# filters_V1_1_Carlos.net
KiCad netlist of a schematic drawn in EAGLE
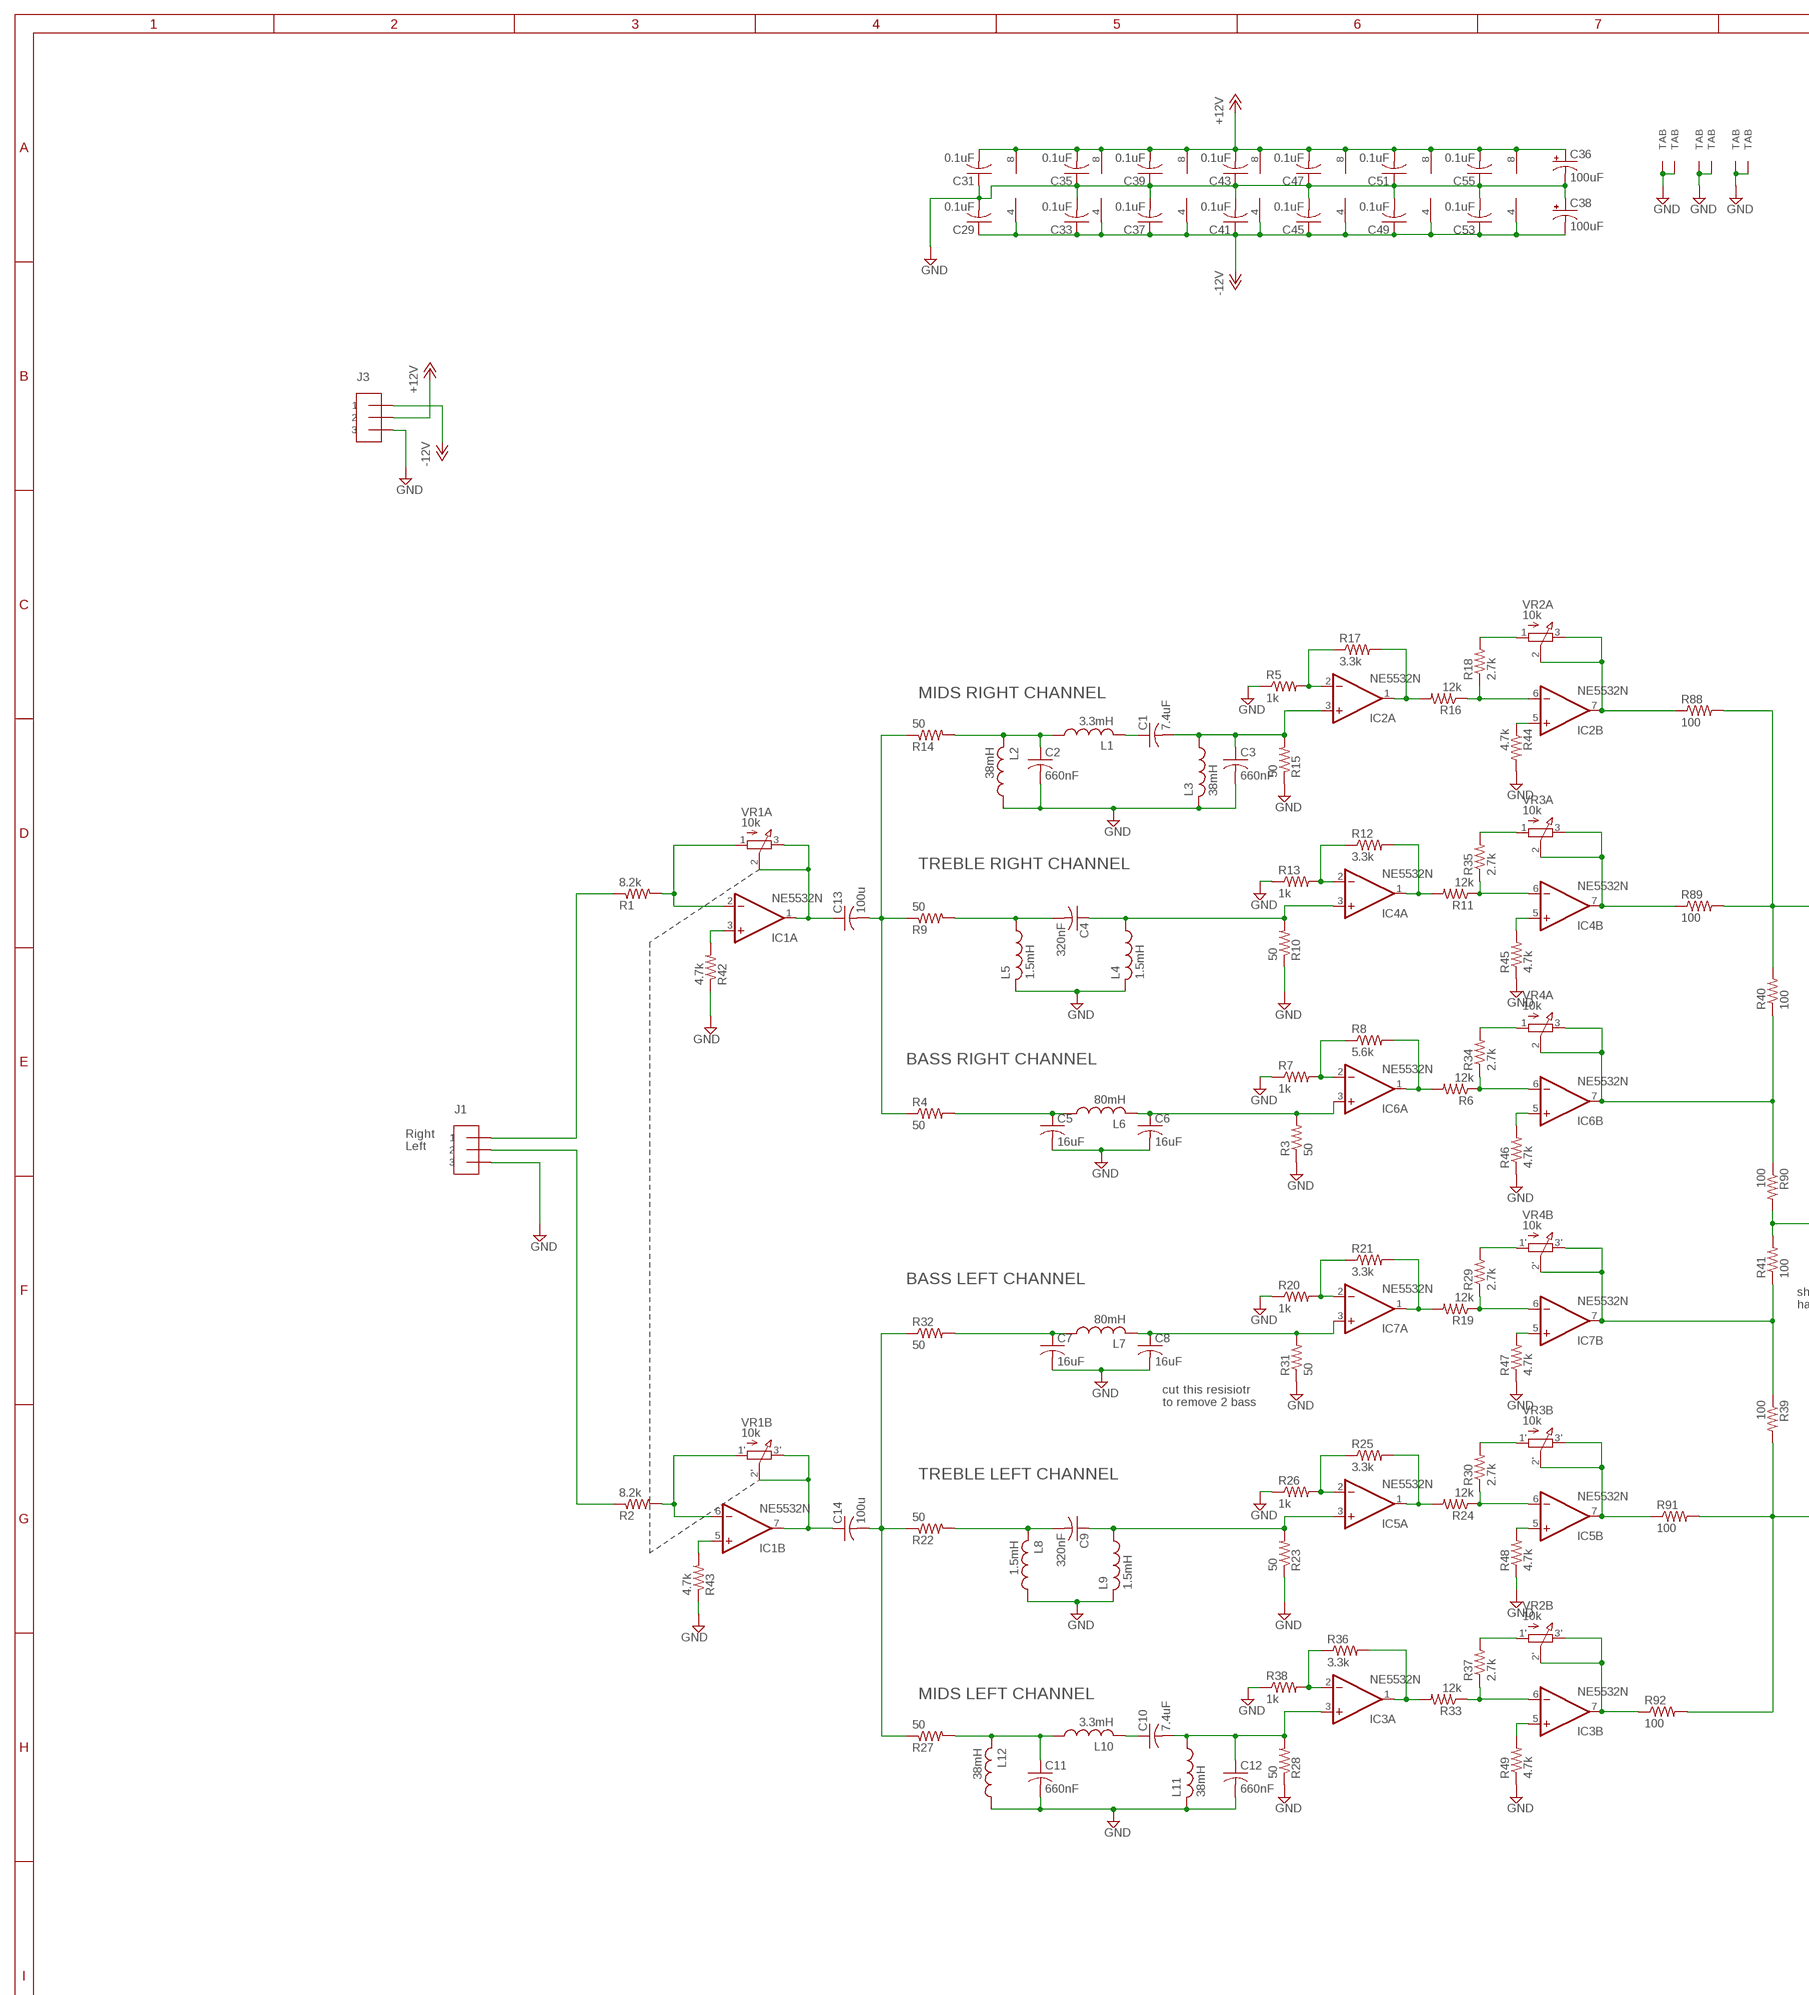
[diagram p0: schematic, sheet 1, part 1 of 2]
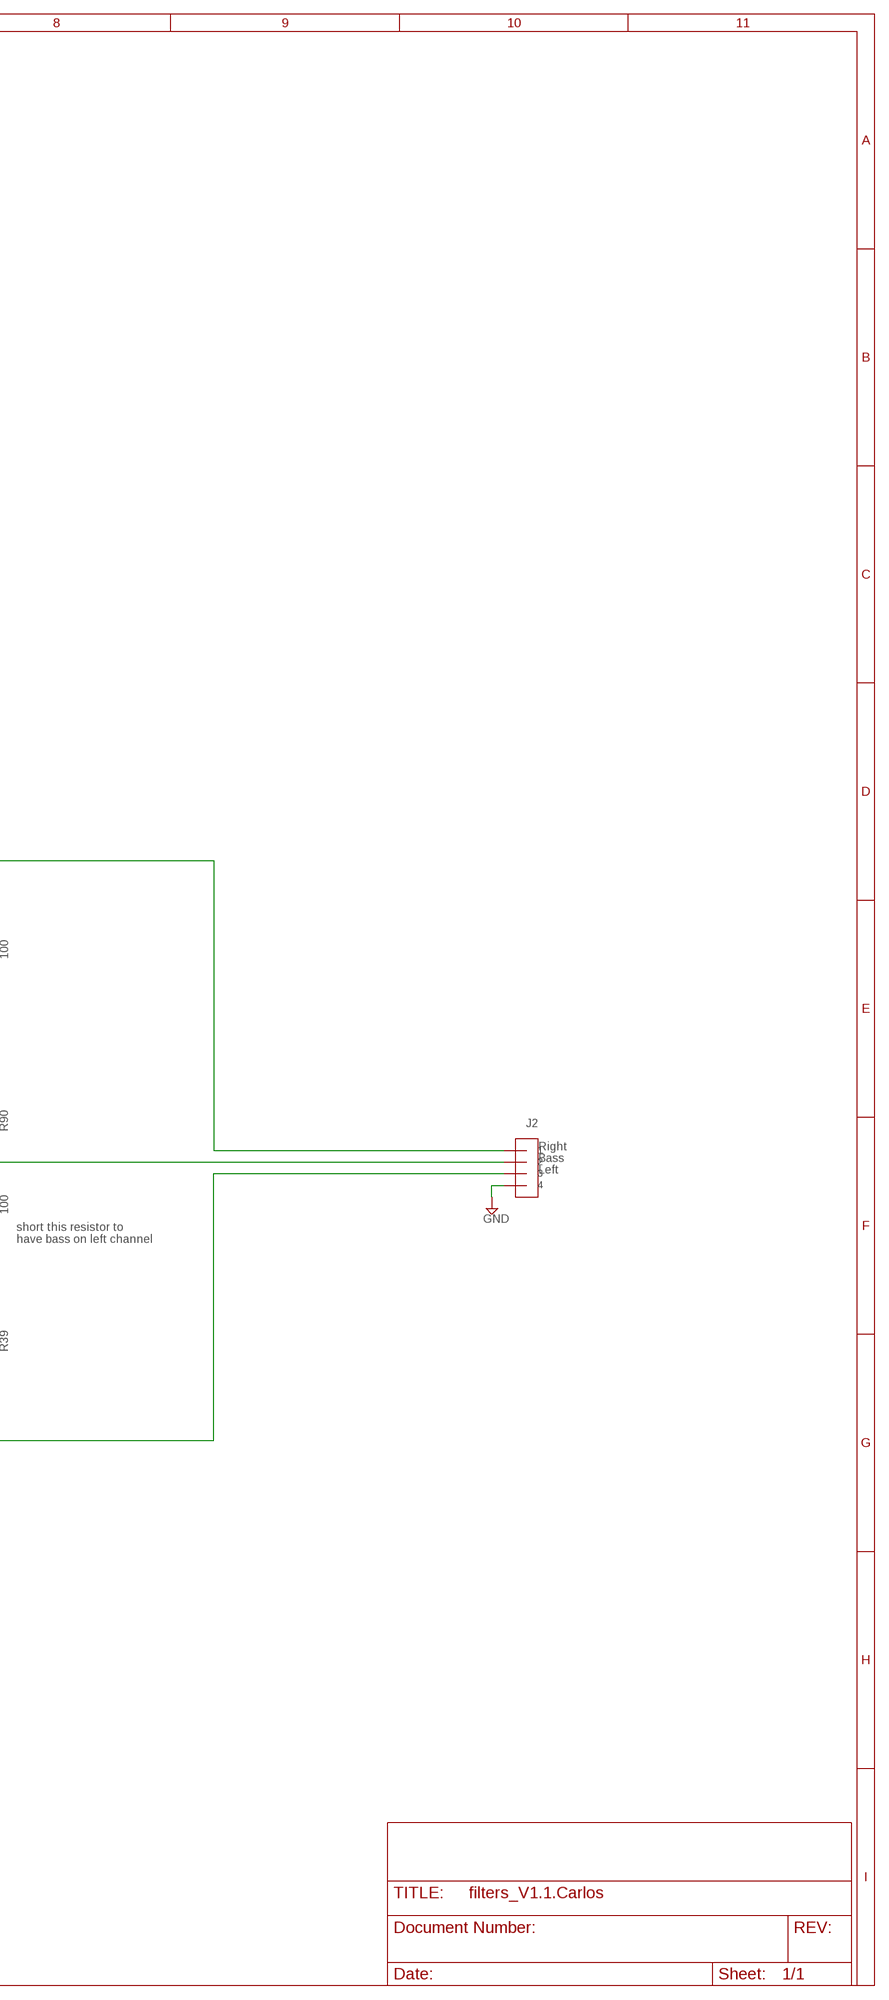
[diagram p1: schematic, sheet 1, part 2 of 2]

(export (version "E")
  (design (tool "Eeschema 10.0.6"))
  (components
    (comp (ref "C1")
      (value "7.4uF")
      (footprint "eagle-import:C050-024X044")
      (libsource (lib "eagle-import") (part "C-US050-024X044"))
    )
    (comp (ref "C2")
      (value "660nF")
      (footprint "eagle-import:C050-024X044")
      (libsource (lib "eagle-import") (part "C-US050-024X044"))
    )
    (comp (ref "C3")
      (value "660nF")
      (footprint "eagle-import:C050-024X044")
      (libsource (lib "eagle-import") (part "C-US050-024X044"))
    )
    (comp (ref "C4")
      (value "320nF")
      (footprint "eagle-import:C050-024X044")
      (libsource (lib "eagle-import") (part "C-US050-024X044"))
    )
    (comp (ref "C5")
      (value "16uF")
      (footprint "eagle-import:C050-024X044")
      (libsource (lib "eagle-import") (part "C-US050-024X044"))
    )
    (comp (ref "C6")
      (value "16uF")
      (footprint "eagle-import:C050-024X044")
      (libsource (lib "eagle-import") (part "C-US050-024X044"))
    )
    (comp (ref "C7")
      (value "16uF")
      (footprint "eagle-import:C050-024X044")
      (libsource (lib "eagle-import") (part "C-US050-024X044"))
    )
    (comp (ref "C8")
      (value "16uF")
      (footprint "eagle-import:C050-024X044")
      (libsource (lib "eagle-import") (part "C-US050-024X044"))
    )
    (comp (ref "C9")
      (value "320nF")
      (footprint "eagle-import:C050-024X044")
      (libsource (lib "eagle-import") (part "C-US050-024X044"))
    )
    (comp (ref "C10")
      (value "7.4uF")
      (footprint "eagle-import:C050-024X044")
      (libsource (lib "eagle-import") (part "C-US050-024X044"))
    )
    (comp (ref "C11")
      (value "660nF")
      (footprint "eagle-import:C050-024X044")
      (libsource (lib "eagle-import") (part "C-US050-024X044"))
    )
    (comp (ref "C12")
      (value "660nF")
      (footprint "eagle-import:C050-024X044")
      (libsource (lib "eagle-import") (part "C-US050-024X044"))
    )
    (comp (ref "C13")
      (value "100u")
      (footprint "eagle-import:C050-024X044")
      (libsource (lib "eagle-import") (part "C-US050-024X044"))
    )
    (comp (ref "C14")
      (value "100u")
      (footprint "eagle-import:C050-024X044")
      (libsource (lib "eagle-import") (part "C-US050-024X044"))
    )
    (comp (ref "C29")
      (value "0.1uF")
      (footprint "eagle-import:C050-024X044")
      (libsource (lib "eagle-import") (part "C-US050-024X044"))
    )
    (comp (ref "C31")
      (value "0.1uF")
      (footprint "eagle-import:C050-024X044")
      (libsource (lib "eagle-import") (part "C-US050-024X044"))
    )
    (comp (ref "C33")
      (value "0.1uF")
      (footprint "eagle-import:C050-024X044")
      (libsource (lib "eagle-import") (part "C-US050-024X044"))
    )
    (comp (ref "C35")
      (value "0.1uF")
      (footprint "eagle-import:C050-024X044")
      (libsource (lib "eagle-import") (part "C-US050-024X044"))
    )
    (comp (ref "C36")
      (value "100uF")
      (footprint "eagle-import:E2,5-6")
      (libsource (lib "eagle-import") (part "CPOL-USE2.5-6"))
    )
    (comp (ref "C37")
      (value "0.1uF")
      (footprint "eagle-import:C050-024X044")
      (libsource (lib "eagle-import") (part "C-US050-024X044"))
    )
    (comp (ref "C38")
      (value "100uF")
      (footprint "eagle-import:E2,5-6")
      (libsource (lib "eagle-import") (part "CPOL-USE2.5-6"))
    )
    (comp (ref "C39")
      (value "0.1uF")
      (footprint "eagle-import:C050-024X044")
      (libsource (lib "eagle-import") (part "C-US050-024X044"))
    )
    (comp (ref "C41")
      (value "0.1uF")
      (footprint "eagle-import:C050-024X044")
      (libsource (lib "eagle-import") (part "C-US050-024X044"))
    )
    (comp (ref "C43")
      (value "0.1uF")
      (footprint "eagle-import:C050-024X044")
      (libsource (lib "eagle-import") (part "C-US050-024X044"))
    )
    (comp (ref "C45")
      (value "0.1uF")
      (footprint "eagle-import:C050-024X044")
      (libsource (lib "eagle-import") (part "C-US050-024X044"))
    )
    (comp (ref "C47")
      (value "0.1uF")
      (footprint "eagle-import:C050-024X044")
      (libsource (lib "eagle-import") (part "C-US050-024X044"))
    )
    (comp (ref "C49")
      (value "0.1uF")
      (footprint "eagle-import:C050-024X044")
      (libsource (lib "eagle-import") (part "C-US050-024X044"))
    )
    (comp (ref "C51")
      (value "0.1uF")
      (footprint "eagle-import:C050-024X044")
      (libsource (lib "eagle-import") (part "C-US050-024X044"))
    )
    (comp (ref "C53")
      (value "0.1uF")
      (footprint "eagle-import:C050-024X044")
      (libsource (lib "eagle-import") (part "C-US050-024X044"))
    )
    (comp (ref "C55")
      (value "0.1uF")
      (footprint "eagle-import:C050-024X044")
      (libsource (lib "eagle-import") (part "C-US050-024X044"))
    )
    (comp (ref "IC1")
      (value "NE5532N")
      (footprint "eagle-import:DIL08")
      (libsource (lib "eagle-import") (part "NE5532N"))
    )
    (comp (ref "IC2")
      (value "NE5532N")
      (footprint "eagle-import:DIL08")
      (libsource (lib "eagle-import") (part "NE5532N"))
    )
    (comp (ref "IC3")
      (value "NE5532N")
      (footprint "eagle-import:DIL08")
      (libsource (lib "eagle-import") (part "NE5532N"))
    )
    (comp (ref "IC4")
      (value "NE5532N")
      (footprint "eagle-import:DIL08")
      (libsource (lib "eagle-import") (part "NE5532N"))
    )
    (comp (ref "IC5")
      (value "NE5532N")
      (footprint "eagle-import:DIL08")
      (libsource (lib "eagle-import") (part "NE5532N"))
    )
    (comp (ref "IC6")
      (value "NE5532N")
      (footprint "eagle-import:DIL08")
      (libsource (lib "eagle-import") (part "NE5532N"))
    )
    (comp (ref "IC7")
      (value "NE5532N")
      (footprint "eagle-import:DIL08")
      (libsource (lib "eagle-import") (part "NE5532N"))
    )
    (comp (ref "J1")
      (value "3_PIN_AMPCONN")
      (footprint "eagle-import:3_PIN_AMPCONN")
      (libsource (lib "eagle-import") (part "3_PIN_AMPCONN"))
    )
    (comp (ref "J2")
      (value "4_PIN_AMPCONN")
      (footprint "eagle-import:4_PIN_AMPCON")
      (libsource (lib "eagle-import") (part "4_PIN_AMPCONN"))
    )
    (comp (ref "J3")
      (value "3_PIN_AMPCONN")
      (footprint "eagle-import:3_PIN_AMPCONN")
      (libsource (lib "eagle-import") (part "3_PIN_AMPCONN"))
    )
    (comp (ref "L1")
      (value "3.3mH")
      (footprint "eagle-import:6000-XXXX-RC")
      (libsource (lib "eagle-import") (part "L-US6000-XXX-RC"))
    )
    (comp (ref "L2")
      (value "38mH")
      (footprint "eagle-import:6000-XXXX-RC")
      (libsource (lib "eagle-import") (part "L-US6000-XXX-RC"))
    )
    (comp (ref "L3")
      (value "38mH")
      (footprint "eagle-import:6000-XXXX-RC")
      (libsource (lib "eagle-import") (part "L-US6000-XXX-RC"))
    )
    (comp (ref "L4")
      (value "1.5mH")
      (footprint "eagle-import:6000-XXXX-RC")
      (libsource (lib "eagle-import") (part "L-US6000-XXX-RC"))
    )
    (comp (ref "L5")
      (value "1.5mH")
      (footprint "eagle-import:6000-XXXX-RC")
      (libsource (lib "eagle-import") (part "L-US6000-XXX-RC"))
    )
    (comp (ref "L6")
      (value "80mH")
      (footprint "eagle-import:6000-XXXX-RC")
      (libsource (lib "eagle-import") (part "L-US6000-XXX-RC"))
    )
    (comp (ref "L7")
      (value "80mH")
      (footprint "eagle-import:6000-XXXX-RC")
      (libsource (lib "eagle-import") (part "L-US6000-XXX-RC"))
    )
    (comp (ref "L8")
      (value "1.5mH")
      (footprint "eagle-import:6000-XXXX-RC")
      (libsource (lib "eagle-import") (part "L-US6000-XXX-RC"))
    )
    (comp (ref "L9")
      (value "1.5mH")
      (footprint "eagle-import:6000-XXXX-RC")
      (libsource (lib "eagle-import") (part "L-US6000-XXX-RC"))
    )
    (comp (ref "L10")
      (value "3.3mH")
      (footprint "eagle-import:6000-XXXX-RC")
      (libsource (lib "eagle-import") (part "L-US6000-XXX-RC"))
    )
    (comp (ref "L11")
      (value "38mH")
      (footprint "eagle-import:6000-XXXX-RC")
      (libsource (lib "eagle-import") (part "L-US6000-XXX-RC"))
    )
    (comp (ref "L12")
      (value "38mH")
      (footprint "eagle-import:6000-XXXX-RC")
      (libsource (lib "eagle-import") (part "L-US6000-XXX-RC"))
    )
    (comp (ref "R1")
      (value "8.2k")
      (footprint "eagle-import:0204V")
      (libsource (lib "eagle-import") (part "R-US_0204/2V"))
    )
    (comp (ref "R2")
      (value "8.2k")
      (footprint "eagle-import:0204V")
      (libsource (lib "eagle-import") (part "R-US_0204/2V"))
    )
    (comp (ref "R3")
      (value "50")
      (footprint "eagle-import:0204V")
      (libsource (lib "eagle-import") (part "R-US_0204/2V"))
    )
    (comp (ref "R4")
      (value "50")
      (footprint "eagle-import:0204V")
      (libsource (lib "eagle-import") (part "R-US_0204/2V"))
    )
    (comp (ref "R5")
      (value "1k")
      (footprint "eagle-import:0204V")
      (libsource (lib "eagle-import") (part "R-US_0204/2V"))
    )
    (comp (ref "R6")
      (value "12k")
      (footprint "eagle-import:0204V")
      (libsource (lib "eagle-import") (part "R-US_0204/2V"))
    )
    (comp (ref "R7")
      (value "1k")
      (footprint "eagle-import:0204V")
      (libsource (lib "eagle-import") (part "R-US_0204/2V"))
    )
    (comp (ref "R8")
      (value "5.6k")
      (footprint "eagle-import:0204V")
      (libsource (lib "eagle-import") (part "R-US_0204/2V"))
    )
    (comp (ref "R9")
      (value "50")
      (footprint "eagle-import:0204V")
      (libsource (lib "eagle-import") (part "R-US_0204/2V"))
    )
    (comp (ref "R10")
      (value "50")
      (footprint "eagle-import:0204V")
      (libsource (lib "eagle-import") (part "R-US_0204/2V"))
    )
    (comp (ref "R11")
      (value "12k")
      (footprint "eagle-import:0204V")
      (libsource (lib "eagle-import") (part "R-US_0204/2V"))
    )
    (comp (ref "R12")
      (value "3.3k")
      (footprint "eagle-import:0204V")
      (libsource (lib "eagle-import") (part "R-US_0204/2V"))
    )
    (comp (ref "R13")
      (value "1k")
      (footprint "eagle-import:0204V")
      (libsource (lib "eagle-import") (part "R-US_0204/2V"))
    )
    (comp (ref "R14")
      (value "50")
      (footprint "eagle-import:0204V")
      (libsource (lib "eagle-import") (part "R-US_0204/2V"))
    )
    (comp (ref "R15")
      (value "50")
      (footprint "eagle-import:0204V")
      (libsource (lib "eagle-import") (part "R-US_0204/2V"))
    )
    (comp (ref "R16")
      (value "12k")
      (footprint "eagle-import:0204V")
      (libsource (lib "eagle-import") (part "R-US_0204/2V"))
    )
    (comp (ref "R17")
      (value "3.3k")
      (footprint "eagle-import:0204V")
      (libsource (lib "eagle-import") (part "R-US_0204/2V"))
    )
    (comp (ref "R18")
      (value "2.7k")
      (footprint "eagle-import:0204V")
      (libsource (lib "eagle-import") (part "R-US_0204/2V"))
    )
    (comp (ref "R19")
      (value "12k")
      (footprint "eagle-import:0204V")
      (libsource (lib "eagle-import") (part "R-US_0204/2V"))
    )
    (comp (ref "R20")
      (value "1k")
      (footprint "eagle-import:0204V")
      (libsource (lib "eagle-import") (part "R-US_0204/2V"))
    )
    (comp (ref "R21")
      (value "3.3k")
      (footprint "eagle-import:0204V")
      (libsource (lib "eagle-import") (part "R-US_0204/2V"))
    )
    (comp (ref "R22")
      (value "50")
      (footprint "eagle-import:0204V")
      (libsource (lib "eagle-import") (part "R-US_0204/2V"))
    )
    (comp (ref "R23")
      (value "50")
      (footprint "eagle-import:0204V")
      (libsource (lib "eagle-import") (part "R-US_0204/2V"))
    )
    (comp (ref "R24")
      (value "12k")
      (footprint "eagle-import:0204V")
      (libsource (lib "eagle-import") (part "R-US_0204/2V"))
    )
    (comp (ref "R25")
      (value "3.3k")
      (footprint "eagle-import:0204V")
      (libsource (lib "eagle-import") (part "R-US_0204/2V"))
    )
    (comp (ref "R26")
      (value "1k")
      (footprint "eagle-import:0204V")
      (libsource (lib "eagle-import") (part "R-US_0204/2V"))
    )
    (comp (ref "R27")
      (value "50")
      (footprint "eagle-import:0204V")
      (libsource (lib "eagle-import") (part "R-US_0204/2V"))
    )
    (comp (ref "R28")
      (value "50")
      (footprint "eagle-import:0204V")
      (libsource (lib "eagle-import") (part "R-US_0204/2V"))
    )
    (comp (ref "R29")
      (value "2.7k")
      (footprint "eagle-import:0204V")
      (libsource (lib "eagle-import") (part "R-US_0204/2V"))
    )
    (comp (ref "R30")
      (value "2.7k")
      (footprint "eagle-import:0204V")
      (libsource (lib "eagle-import") (part "R-US_0204/2V"))
    )
    (comp (ref "R31")
      (value "50")
      (footprint "eagle-import:0204V")
      (libsource (lib "eagle-import") (part "R-US_0204/2V"))
    )
    (comp (ref "R32")
      (value "50")
      (footprint "eagle-import:0204V")
      (libsource (lib "eagle-import") (part "R-US_0204/2V"))
    )
    (comp (ref "R33")
      (value "12k")
      (footprint "eagle-import:0204V")
      (libsource (lib "eagle-import") (part "R-US_0204/2V"))
    )
    (comp (ref "R34")
      (value "2.7k")
      (footprint "eagle-import:0204V")
      (libsource (lib "eagle-import") (part "R-US_0204/2V"))
    )
    (comp (ref "R35")
      (value "2.7k")
      (footprint "eagle-import:0204V")
      (libsource (lib "eagle-import") (part "R-US_0204/2V"))
    )
    (comp (ref "R36")
      (value "3.3k")
      (footprint "eagle-import:0204V")
      (libsource (lib "eagle-import") (part "R-US_0204/2V"))
    )
    (comp (ref "R37")
      (value "2.7k")
      (footprint "eagle-import:0204V")
      (libsource (lib "eagle-import") (part "R-US_0204/2V"))
    )
    (comp (ref "R38")
      (value "1k")
      (footprint "eagle-import:0204V")
      (libsource (lib "eagle-import") (part "R-US_0204/2V"))
    )
    (comp (ref "R39")
      (value "100")
      (footprint "eagle-import:0204V")
      (libsource (lib "eagle-import") (part "R-US_0204/2V"))
    )
    (comp (ref "R40")
      (value "100")
      (footprint "eagle-import:0204V")
      (libsource (lib "eagle-import") (part "R-US_0204/2V"))
    )
    (comp (ref "R41")
      (value "100")
      (footprint "eagle-import:0204V")
      (libsource (lib "eagle-import") (part "R-US_0204/2V"))
    )
    (comp (ref "R42")
      (value "4.7k")
      (footprint "eagle-import:0204V")
      (libsource (lib "eagle-import") (part "R-US_0204/2V"))
    )
    (comp (ref "R43")
      (value "4.7k")
      (footprint "eagle-import:0204V")
      (libsource (lib "eagle-import") (part "R-US_0204/2V"))
    )
    (comp (ref "R44")
      (value "4.7k")
      (footprint "eagle-import:0204V")
      (libsource (lib "eagle-import") (part "R-US_0204/2V"))
    )
    (comp (ref "R45")
      (value "4.7k")
      (footprint "eagle-import:0204V")
      (libsource (lib "eagle-import") (part "R-US_0204/2V"))
    )
    (comp (ref "R46")
      (value "4.7k")
      (footprint "eagle-import:0204V")
      (libsource (lib "eagle-import") (part "R-US_0204/2V"))
    )
    (comp (ref "R47")
      (value "4.7k")
      (footprint "eagle-import:0204V")
      (libsource (lib "eagle-import") (part "R-US_0204/2V"))
    )
    (comp (ref "R48")
      (value "4.7k")
      (footprint "eagle-import:0204V")
      (libsource (lib "eagle-import") (part "R-US_0204/2V"))
    )
    (comp (ref "R49")
      (value "4.7k")
      (footprint "eagle-import:0204V")
      (libsource (lib "eagle-import") (part "R-US_0204/2V"))
    )
    (comp (ref "R88")
      (value "100")
      (footprint "eagle-import:0204V")
      (libsource (lib "eagle-import") (part "R-US_0204/2V"))
    )
    (comp (ref "R89")
      (value "100")
      (footprint "eagle-import:0204V")
      (libsource (lib "eagle-import") (part "R-US_0204/2V"))
    )
    (comp (ref "R90")
      (value "100")
      (footprint "eagle-import:0204V")
      (libsource (lib "eagle-import") (part "R-US_0204/2V"))
    )
    (comp (ref "R91")
      (value "100")
      (footprint "eagle-import:0204V")
      (libsource (lib "eagle-import") (part "R-US_0204/2V"))
    )
    (comp (ref "R92")
      (value "100")
      (footprint "eagle-import:0204V")
      (libsource (lib "eagle-import") (part "R-US_0204/2V"))
    )
    (comp (ref "VR1")
      (value "10k")
      (footprint "eagle-import:VOL_POT_2GANG")
      (libsource (lib "eagle-import") (part "VOL_POT_2GANG"))
    )
    (comp (ref "VR2")
      (value "10k")
      (footprint "eagle-import:TONE_POT_2GANG")
      (libsource (lib "eagle-import") (part "P140KV1-F25BR"))
    )
    (comp (ref "VR3")
      (value "10k")
      (footprint "eagle-import:TONE_POT_2GANG")
      (libsource (lib "eagle-import") (part "P140KV1-F25BR"))
    )
    (comp (ref "VR4")
      (value "10k")
      (footprint "eagle-import:TONE_POT_2GANG")
      (libsource (lib "eagle-import") (part "P140KV1-F25BR"))
    )
  )
  (nets
    (net (code "1") (name "+12V") (class "Default")
      (node (ref "C31") (pin "2") (pinfunction "2_2") (pintype "passive"))
      (node (ref "C35") (pin "2") (pinfunction "2_2") (pintype "passive"))
      (node (ref "C36") (pin "+") (pinfunction "+_+") (pintype "passive"))
      (node (ref "C39") (pin "2") (pinfunction "2_2") (pintype "passive"))
      (node (ref "C43") (pin "2") (pinfunction "2_2") (pintype "passive"))
      (node (ref "C47") (pin "2") (pinfunction "2_2") (pintype "passive"))
      (node (ref "C51") (pin "2") (pinfunction "2_2") (pintype "passive"))
      (node (ref "C55") (pin "2") (pinfunction "2_2") (pintype "passive"))
      (node (ref "IC1") (pin "8") (pinfunction "V+_8") (pintype "power_in"))
      (node (ref "IC2") (pin "8") (pinfunction "V+_8") (pintype "power_in"))
      (node (ref "IC3") (pin "8") (pinfunction "V+_8") (pintype "power_in"))
      (node (ref "IC4") (pin "8") (pinfunction "V+_8") (pintype "power_in"))
      (node (ref "IC5") (pin "8") (pinfunction "V+_8") (pintype "power_in"))
      (node (ref "IC6") (pin "8") (pinfunction "V+_8") (pintype "power_in"))
      (node (ref "IC7") (pin "8") (pinfunction "V+_8") (pintype "power_in"))
      (node (ref "J3") (pin "2") (pinfunction "2_2") (pintype "passive"))
    )
    (net (code "2") (name "-12V") (class "Default")
      (node (ref "C29") (pin "1") (pinfunction "1_1") (pintype "passive"))
      (node (ref "C33") (pin "1") (pinfunction "1_1") (pintype "passive"))
      (node (ref "C37") (pin "1") (pinfunction "1_1") (pintype "passive"))
      (node (ref "C38") (pin "-") (pinfunction "-_-") (pintype "passive"))
      (node (ref "C41") (pin "1") (pinfunction "1_1") (pintype "passive"))
      (node (ref "C45") (pin "1") (pinfunction "1_1") (pintype "passive"))
      (node (ref "C49") (pin "1") (pinfunction "1_1") (pintype "passive"))
      (node (ref "C53") (pin "1") (pinfunction "1_1") (pintype "passive"))
      (node (ref "IC1") (pin "4") (pinfunction "V-_4") (pintype "power_in"))
      (node (ref "IC2") (pin "4") (pinfunction "V-_4") (pintype "power_in"))
      (node (ref "IC3") (pin "4") (pinfunction "V-_4") (pintype "power_in"))
      (node (ref "IC4") (pin "4") (pinfunction "V-_4") (pintype "power_in"))
      (node (ref "IC5") (pin "4") (pinfunction "V-_4") (pintype "power_in"))
      (node (ref "IC6") (pin "4") (pinfunction "V-_4") (pintype "power_in"))
      (node (ref "IC7") (pin "4") (pinfunction "V-_4") (pintype "power_in"))
      (node (ref "J3") (pin "1") (pinfunction "1_1") (pintype "passive"))
    )
    (net (code "3") (name "GND") (class "Default")
      (node (ref "C11") (pin "2") (pinfunction "2_2") (pintype "passive"))
      (node (ref "C12") (pin "2") (pinfunction "2_2") (pintype "passive"))
      (node (ref "C2") (pin "2") (pinfunction "2_2") (pintype "passive"))
      (node (ref "C29") (pin "2") (pinfunction "2_2") (pintype "passive"))
      (node (ref "C3") (pin "2") (pinfunction "2_2") (pintype "passive"))
      (node (ref "C31") (pin "1") (pinfunction "1_1") (pintype "passive"))
      (node (ref "C33") (pin "2") (pinfunction "2_2") (pintype "passive"))
      (node (ref "C35") (pin "1") (pinfunction "1_1") (pintype "passive"))
      (node (ref "C36") (pin "-") (pinfunction "-_-") (pintype "passive"))
      (node (ref "C37") (pin "2") (pinfunction "2_2") (pintype "passive"))
      (node (ref "C38") (pin "+") (pinfunction "+_+") (pintype "passive"))
      (node (ref "C39") (pin "1") (pinfunction "1_1") (pintype "passive"))
      (node (ref "C41") (pin "2") (pinfunction "2_2") (pintype "passive"))
      (node (ref "C43") (pin "1") (pinfunction "1_1") (pintype "passive"))
      (node (ref "C45") (pin "2") (pinfunction "2_2") (pintype "passive"))
      (node (ref "C47") (pin "1") (pinfunction "1_1") (pintype "passive"))
      (node (ref "C49") (pin "2") (pinfunction "2_2") (pintype "passive"))
      (node (ref "C5") (pin "2") (pinfunction "2_2") (pintype "passive"))
      (node (ref "C51") (pin "1") (pinfunction "1_1") (pintype "passive"))
      (node (ref "C53") (pin "2") (pinfunction "2_2") (pintype "passive"))
      (node (ref "C55") (pin "1") (pinfunction "1_1") (pintype "passive"))
      (node (ref "C6") (pin "2") (pinfunction "2_2") (pintype "passive"))
      (node (ref "C7") (pin "2") (pinfunction "2_2") (pintype "passive"))
      (node (ref "C8") (pin "2") (pinfunction "2_2") (pintype "passive"))
      (node (ref "J1") (pin "3") (pinfunction "3_3") (pintype "passive"))
      (node (ref "J2") (pin "4") (pinfunction "4_4") (pintype "passive"))
      (node (ref "J3") (pin "3") (pinfunction "3_3") (pintype "passive"))
      (node (ref "L11") (pin "2") (pinfunction "2_2") (pintype "passive"))
      (node (ref "L12") (pin "1") (pinfunction "1_1") (pintype "passive"))
      (node (ref "L2") (pin "1") (pinfunction "1_1") (pintype "passive"))
      (node (ref "L3") (pin "2") (pinfunction "2_2") (pintype "passive"))
      (node (ref "L4") (pin "2") (pinfunction "2_2") (pintype "passive"))
      (node (ref "L5") (pin "2") (pinfunction "2_2") (pintype "passive"))
      (node (ref "L8") (pin "1") (pinfunction "1_1") (pintype "passive"))
      (node (ref "L9") (pin "2") (pinfunction "2_2") (pintype "passive"))
      (node (ref "R10") (pin "1") (pinfunction "1_1") (pintype "passive"))
      (node (ref "R13") (pin "1") (pinfunction "1_1") (pintype "passive"))
      (node (ref "R15") (pin "1") (pinfunction "1_1") (pintype "passive"))
      (node (ref "R20") (pin "1") (pinfunction "1_1") (pintype "passive"))
      (node (ref "R23") (pin "1") (pinfunction "1_1") (pintype "passive"))
      (node (ref "R26") (pin "1") (pinfunction "1_1") (pintype "passive"))
      (node (ref "R28") (pin "1") (pinfunction "1_1") (pintype "passive"))
      (node (ref "R3") (pin "1") (pinfunction "1_1") (pintype "passive"))
      (node (ref "R31") (pin "1") (pinfunction "1_1") (pintype "passive"))
      (node (ref "R38") (pin "1") (pinfunction "1_1") (pintype "passive"))
      (node (ref "R42") (pin "1") (pinfunction "1_1") (pintype "passive"))
      (node (ref "R43") (pin "1") (pinfunction "1_1") (pintype "passive"))
      (node (ref "R44") (pin "2") (pinfunction "2_2") (pintype "passive"))
      (node (ref "R45") (pin "1") (pinfunction "1_1") (pintype "passive"))
      (node (ref "R46") (pin "1") (pinfunction "1_1") (pintype "passive"))
      (node (ref "R47") (pin "1") (pinfunction "1_1") (pintype "passive"))
      (node (ref "R48") (pin "1") (pinfunction "1_1") (pintype "passive"))
      (node (ref "R49") (pin "1") (pinfunction "1_1") (pintype "passive"))
      (node (ref "R5") (pin "1") (pinfunction "1_1") (pintype "passive"))
      (node (ref "R7") (pin "1") (pinfunction "1_1") (pintype "passive"))
      (node (ref "VR2") (pin "P$3") (pinfunction "TAB_P$3") (pintype "passive"))
      (node (ref "VR2") (pin "P$4") (pinfunction "TAB_P$4") (pintype "passive"))
      (node (ref "VR3") (pin "P$3") (pinfunction "TAB_P$3") (pintype "passive"))
      (node (ref "VR3") (pin "P$4") (pinfunction "TAB_P$4") (pintype "passive"))
      (node (ref "VR4") (pin "P$3") (pinfunction "TAB_P$3") (pintype "passive"))
      (node (ref "VR4") (pin "P$4") (pinfunction "TAB_P$4") (pintype "passive"))
    )
    (net (code "4") (name "Net-(C1-Pad1)") (class "Default")
      (node (ref "C1") (pin "1") (pinfunction "1_1") (pintype "passive"))
      (node (ref "L1") (pin "2") (pinfunction "2_2") (pintype "passive"))
    )
    (net (code "5") (name "Net-(C2-Pad1)") (class "Default")
      (node (ref "C2") (pin "1") (pinfunction "1_1") (pintype "passive"))
      (node (ref "L1") (pin "1") (pinfunction "1_1") (pintype "passive"))
      (node (ref "L2") (pin "2") (pinfunction "2_2") (pintype "passive"))
      (node (ref "R14") (pin "2") (pinfunction "2_2") (pintype "passive"))
    )
    (net (code "6") (name "Net-(C4-Pad2)") (class "Default")
      (node (ref "C4") (pin "2") (pinfunction "2_2") (pintype "passive"))
      (node (ref "L5") (pin "1") (pinfunction "1_1") (pintype "passive"))
      (node (ref "R9") (pin "2") (pinfunction "2_2") (pintype "passive"))
    )
    (net (code "7") (name "Net-(C5-Pad1)") (class "Default")
      (node (ref "C5") (pin "1") (pinfunction "1_1") (pintype "passive"))
      (node (ref "L6") (pin "1") (pinfunction "1_1") (pintype "passive"))
      (node (ref "R4") (pin "2") (pinfunction "2_2") (pintype "passive"))
    )
    (net (code "8") (name "Net-(C7-Pad1)") (class "Default")
      (node (ref "C7") (pin "1") (pinfunction "1_1") (pintype "passive"))
      (node (ref "L7") (pin "1") (pinfunction "1_1") (pintype "passive"))
      (node (ref "R32") (pin "2") (pinfunction "2_2") (pintype "passive"))
    )
    (net (code "9") (name "Net-(C9-Pad2)") (class "Default")
      (node (ref "C9") (pin "2") (pinfunction "2_2") (pintype "passive"))
      (node (ref "L8") (pin "2") (pinfunction "2_2") (pintype "passive"))
      (node (ref "R22") (pin "2") (pinfunction "2_2") (pintype "passive"))
    )
    (net (code "10") (name "Net-(C10-Pad1)") (class "Default")
      (node (ref "C10") (pin "1") (pinfunction "1_1") (pintype "passive"))
      (node (ref "L10") (pin "2") (pinfunction "2_2") (pintype "passive"))
    )
    (net (code "11") (name "Net-(C11-Pad1)") (class "Default")
      (node (ref "C11") (pin "1") (pinfunction "1_1") (pintype "passive"))
      (node (ref "L10") (pin "1") (pinfunction "1_1") (pintype "passive"))
      (node (ref "L12") (pin "2") (pinfunction "2_2") (pintype "passive"))
      (node (ref "R27") (pin "2") (pinfunction "2_2") (pintype "passive"))
    )
    (net (code "12") (name "Net-(C13-Pad2)") (class "Default")
      (node (ref "C13") (pin "2") (pinfunction "2_2") (pintype "passive"))
      (node (ref "R14") (pin "1") (pinfunction "1_1") (pintype "passive"))
      (node (ref "R4") (pin "1") (pinfunction "1_1") (pintype "passive"))
      (node (ref "R9") (pin "1") (pinfunction "1_1") (pintype "passive"))
    )
    (net (code "13") (name "Net-(C14-Pad2)") (class "Default")
      (node (ref "C14") (pin "2") (pinfunction "2_2") (pintype "passive"))
      (node (ref "R22") (pin "1") (pinfunction "1_1") (pintype "passive"))
      (node (ref "R27") (pin "1") (pinfunction "1_1") (pintype "passive"))
      (node (ref "R32") (pin "1") (pinfunction "1_1") (pintype "passive"))
    )
    (net (code "14") (name "Net-(IC1A-+IN)") (class "Default")
      (node (ref "IC1") (pin "3") (pinfunction "+IN_3") (pintype "input"))
      (node (ref "R42") (pin "2") (pinfunction "2_2") (pintype "passive"))
    )
    (net (code "15") (name "Net-(IC1A--IN)") (class "Default")
      (node (ref "IC1") (pin "2") (pinfunction "-IN_2") (pintype "input"))
      (node (ref "R1") (pin "2") (pinfunction "2_2") (pintype "passive"))
      (node (ref "VR1") (pin "1") (pinfunction "1_1") (pintype "passive"))
    )
    (net (code "16") (name "Net-(IC1A-OUT)") (class "Default")
      (node (ref "C13") (pin "1") (pinfunction "1_1") (pintype "passive"))
      (node (ref "IC1") (pin "1") (pinfunction "OUT_1") (pintype "output"))
      (node (ref "VR1") (pin "2") (pinfunction "2_2") (pintype "passive"))
      (node (ref "VR1") (pin "3") (pinfunction "3_3") (pintype "passive"))
    )
    (net (code "17") (name "Net-(IC1B-+IN)") (class "Default")
      (node (ref "IC1") (pin "5") (pinfunction "+IN_5") (pintype "input"))
      (node (ref "R43") (pin "2") (pinfunction "2_2") (pintype "passive"))
    )
    (net (code "18") (name "Net-(IC1B--IN)") (class "Default")
      (node (ref "IC1") (pin "6") (pinfunction "-IN_6") (pintype "input"))
      (node (ref "R2") (pin "2") (pinfunction "2_2") (pintype "passive"))
      (node (ref "VR1") (pin "1'") (pinfunction "1_1'") (pintype "passive"))
    )
    (net (code "19") (name "Net-(IC1B-OUT)") (class "Default")
      (node (ref "C14") (pin "1") (pinfunction "1_1") (pintype "passive"))
      (node (ref "IC1") (pin "7") (pinfunction "OUT_7") (pintype "output"))
      (node (ref "VR1") (pin "2'") (pinfunction "2_2'") (pintype "passive"))
      (node (ref "VR1") (pin "3'") (pinfunction "3_3'") (pintype "passive"))
    )
    (net (code "20") (name "Net-(IC2A-+IN)") (class "Default")
      (node (ref "C1") (pin "2") (pinfunction "2_2") (pintype "passive"))
      (node (ref "C3") (pin "1") (pinfunction "1_1") (pintype "passive"))
      (node (ref "IC2") (pin "3") (pinfunction "+IN_3") (pintype "input"))
      (node (ref "L3") (pin "1") (pinfunction "1_1") (pintype "passive"))
      (node (ref "R15") (pin "2") (pinfunction "2_2") (pintype "passive"))
    )
    (net (code "21") (name "Net-(IC2A--IN)") (class "Default")
      (node (ref "IC2") (pin "2") (pinfunction "-IN_2") (pintype "input"))
      (node (ref "R17") (pin "1") (pinfunction "1_1") (pintype "passive"))
      (node (ref "R5") (pin "2") (pinfunction "2_2") (pintype "passive"))
    )
    (net (code "22") (name "Net-(IC2A-OUT)") (class "Default")
      (node (ref "IC2") (pin "1") (pinfunction "OUT_1") (pintype "output"))
      (node (ref "R16") (pin "2") (pinfunction "2_2") (pintype "passive"))
      (node (ref "R17") (pin "2") (pinfunction "2_2") (pintype "passive"))
    )
    (net (code "23") (name "Net-(IC2B-+IN)") (class "Default")
      (node (ref "IC2") (pin "5") (pinfunction "+IN_5") (pintype "input"))
      (node (ref "R44") (pin "1") (pinfunction "1_1") (pintype "passive"))
    )
    (net (code "24") (name "Net-(IC2B--IN)") (class "Default")
      (node (ref "IC2") (pin "6") (pinfunction "-IN_6") (pintype "input"))
      (node (ref "R16") (pin "1") (pinfunction "1_1") (pintype "passive"))
      (node (ref "R18") (pin "1") (pinfunction "1_1") (pintype "passive"))
    )
    (net (code "25") (name "Net-(IC2B-OUT)") (class "Default")
      (node (ref "IC2") (pin "7") (pinfunction "OUT_7") (pintype "output"))
      (node (ref "R88") (pin "1") (pinfunction "1_1") (pintype "passive"))
      (node (ref "VR2") (pin "2") (pinfunction "1_2_2") (pintype "passive"))
      (node (ref "VR2") (pin "3") (pinfunction "1_3_3") (pintype "passive"))
    )
    (net (code "26") (name "Net-(IC3A-+IN)") (class "Default")
      (node (ref "C10") (pin "2") (pinfunction "2_2") (pintype "passive"))
      (node (ref "C12") (pin "1") (pinfunction "1_1") (pintype "passive"))
      (node (ref "IC3") (pin "3") (pinfunction "+IN_3") (pintype "input"))
      (node (ref "L11") (pin "1") (pinfunction "1_1") (pintype "passive"))
      (node (ref "R28") (pin "2") (pinfunction "2_2") (pintype "passive"))
    )
    (net (code "27") (name "Net-(IC3A--IN)") (class "Default")
      (node (ref "IC3") (pin "2") (pinfunction "-IN_2") (pintype "input"))
      (node (ref "R36") (pin "1") (pinfunction "1_1") (pintype "passive"))
      (node (ref "R38") (pin "2") (pinfunction "2_2") (pintype "passive"))
    )
    (net (code "28") (name "Net-(IC3A-OUT)") (class "Default")
      (node (ref "IC3") (pin "1") (pinfunction "OUT_1") (pintype "output"))
      (node (ref "R33") (pin "2") (pinfunction "2_2") (pintype "passive"))
      (node (ref "R36") (pin "2") (pinfunction "2_2") (pintype "passive"))
    )
    (net (code "29") (name "Net-(IC3B-+IN)") (class "Default")
      (node (ref "IC3") (pin "5") (pinfunction "+IN_5") (pintype "input"))
      (node (ref "R49") (pin "2") (pinfunction "2_2") (pintype "passive"))
    )
    (net (code "30") (name "Net-(IC3B--IN)") (class "Default")
      (node (ref "IC3") (pin "6") (pinfunction "-IN_6") (pintype "input"))
      (node (ref "R33") (pin "1") (pinfunction "1_1") (pintype "passive"))
      (node (ref "R37") (pin "1") (pinfunction "1_1") (pintype "passive"))
    )
    (net (code "31") (name "Net-(IC3B-OUT)") (class "Default")
      (node (ref "IC3") (pin "7") (pinfunction "OUT_7") (pintype "output"))
      (node (ref "R92") (pin "1") (pinfunction "1_1") (pintype "passive"))
      (node (ref "VR2") (pin "2'") (pinfunction "1_2_2'") (pintype "passive"))
      (node (ref "VR2") (pin "3'") (pinfunction "1_3_3'") (pintype "passive"))
    )
    (net (code "32") (name "Net-(IC4A-+IN)") (class "Default")
      (node (ref "C4") (pin "1") (pinfunction "1_1") (pintype "passive"))
      (node (ref "IC4") (pin "3") (pinfunction "+IN_3") (pintype "input"))
      (node (ref "L4") (pin "1") (pinfunction "1_1") (pintype "passive"))
      (node (ref "R10") (pin "2") (pinfunction "2_2") (pintype "passive"))
    )
    (net (code "33") (name "Net-(IC4A--IN)") (class "Default")
      (node (ref "IC4") (pin "2") (pinfunction "-IN_2") (pintype "input"))
      (node (ref "R12") (pin "1") (pinfunction "1_1") (pintype "passive"))
      (node (ref "R13") (pin "2") (pinfunction "2_2") (pintype "passive"))
    )
    (net (code "34") (name "Net-(IC4A-OUT)") (class "Default")
      (node (ref "IC4") (pin "1") (pinfunction "OUT_1") (pintype "output"))
      (node (ref "R11") (pin "2") (pinfunction "2_2") (pintype "passive"))
      (node (ref "R12") (pin "2") (pinfunction "2_2") (pintype "passive"))
    )
    (net (code "35") (name "Net-(IC4B-+IN)") (class "Default")
      (node (ref "IC4") (pin "5") (pinfunction "+IN_5") (pintype "input"))
      (node (ref "R45") (pin "2") (pinfunction "2_2") (pintype "passive"))
    )
    (net (code "36") (name "Net-(IC4B--IN)") (class "Default")
      (node (ref "IC4") (pin "6") (pinfunction "-IN_6") (pintype "input"))
      (node (ref "R11") (pin "1") (pinfunction "1_1") (pintype "passive"))
      (node (ref "R35") (pin "1") (pinfunction "1_1") (pintype "passive"))
    )
    (net (code "37") (name "Net-(IC4B-OUT)") (class "Default")
      (node (ref "IC4") (pin "7") (pinfunction "OUT_7") (pintype "output"))
      (node (ref "R89") (pin "1") (pinfunction "1_1") (pintype "passive"))
      (node (ref "VR3") (pin "2") (pinfunction "1_2_2") (pintype "passive"))
      (node (ref "VR3") (pin "3") (pinfunction "1_3_3") (pintype "passive"))
    )
    (net (code "38") (name "Net-(IC5A-+IN)") (class "Default")
      (node (ref "C9") (pin "1") (pinfunction "1_1") (pintype "passive"))
      (node (ref "IC5") (pin "3") (pinfunction "+IN_3") (pintype "input"))
      (node (ref "L9") (pin "1") (pinfunction "1_1") (pintype "passive"))
      (node (ref "R23") (pin "2") (pinfunction "2_2") (pintype "passive"))
    )
    (net (code "39") (name "Net-(IC5A--IN)") (class "Default")
      (node (ref "IC5") (pin "2") (pinfunction "-IN_2") (pintype "input"))
      (node (ref "R25") (pin "1") (pinfunction "1_1") (pintype "passive"))
      (node (ref "R26") (pin "2") (pinfunction "2_2") (pintype "passive"))
    )
    (net (code "40") (name "Net-(IC5A-OUT)") (class "Default")
      (node (ref "IC5") (pin "1") (pinfunction "OUT_1") (pintype "output"))
      (node (ref "R24") (pin "2") (pinfunction "2_2") (pintype "passive"))
      (node (ref "R25") (pin "2") (pinfunction "2_2") (pintype "passive"))
    )
    (net (code "41") (name "Net-(IC5B-+IN)") (class "Default")
      (node (ref "IC5") (pin "5") (pinfunction "+IN_5") (pintype "input"))
      (node (ref "R48") (pin "2") (pinfunction "2_2") (pintype "passive"))
    )
    (net (code "42") (name "Net-(IC5B--IN)") (class "Default")
      (node (ref "IC5") (pin "6") (pinfunction "-IN_6") (pintype "input"))
      (node (ref "R24") (pin "1") (pinfunction "1_1") (pintype "passive"))
      (node (ref "R30") (pin "1") (pinfunction "1_1") (pintype "passive"))
    )
    (net (code "43") (name "Net-(IC5B-OUT)") (class "Default")
      (node (ref "IC5") (pin "7") (pinfunction "OUT_7") (pintype "output"))
      (node (ref "R91") (pin "1") (pinfunction "1_1") (pintype "passive"))
      (node (ref "VR3") (pin "2'") (pinfunction "1_2_2'") (pintype "passive"))
      (node (ref "VR3") (pin "3'") (pinfunction "1_3_3'") (pintype "passive"))
    )
    (net (code "44") (name "Net-(IC6A-+IN)") (class "Default")
      (node (ref "C6") (pin "1") (pinfunction "1_1") (pintype "passive"))
      (node (ref "IC6") (pin "3") (pinfunction "+IN_3") (pintype "input"))
      (node (ref "L6") (pin "2") (pinfunction "2_2") (pintype "passive"))
      (node (ref "R3") (pin "2") (pinfunction "2_2") (pintype "passive"))
    )
    (net (code "45") (name "Net-(IC6A--IN)") (class "Default")
      (node (ref "IC6") (pin "2") (pinfunction "-IN_2") (pintype "input"))
      (node (ref "R7") (pin "2") (pinfunction "2_2") (pintype "passive"))
      (node (ref "R8") (pin "1") (pinfunction "1_1") (pintype "passive"))
    )
    (net (code "46") (name "Net-(IC6A-OUT)") (class "Default")
      (node (ref "IC6") (pin "1") (pinfunction "OUT_1") (pintype "output"))
      (node (ref "R6") (pin "2") (pinfunction "2_2") (pintype "passive"))
      (node (ref "R8") (pin "2") (pinfunction "2_2") (pintype "passive"))
    )
    (net (code "47") (name "Net-(IC6B-+IN)") (class "Default")
      (node (ref "IC6") (pin "5") (pinfunction "+IN_5") (pintype "input"))
      (node (ref "R46") (pin "2") (pinfunction "2_2") (pintype "passive"))
    )
    (net (code "48") (name "Net-(IC6B--IN)") (class "Default")
      (node (ref "IC6") (pin "6") (pinfunction "-IN_6") (pintype "input"))
      (node (ref "R34") (pin "1") (pinfunction "1_1") (pintype "passive"))
      (node (ref "R6") (pin "1") (pinfunction "1_1") (pintype "passive"))
    )
    (net (code "49") (name "Net-(IC6B-OUT)") (class "Default")
      (node (ref "IC6") (pin "7") (pinfunction "OUT_7") (pintype "output"))
      (node (ref "R40") (pin "1") (pinfunction "1_1") (pintype "passive"))
      (node (ref "R90") (pin "1") (pinfunction "1_1") (pintype "passive"))
      (node (ref "VR4") (pin "2") (pinfunction "1_2_2") (pintype "passive"))
      (node (ref "VR4") (pin "3") (pinfunction "1_3_3") (pintype "passive"))
    )
    (net (code "50") (name "Net-(IC7A-+IN)") (class "Default")
      (node (ref "C8") (pin "1") (pinfunction "1_1") (pintype "passive"))
      (node (ref "IC7") (pin "3") (pinfunction "+IN_3") (pintype "input"))
      (node (ref "L7") (pin "2") (pinfunction "2_2") (pintype "passive"))
      (node (ref "R31") (pin "2") (pinfunction "2_2") (pintype "passive"))
    )
    (net (code "51") (name "Net-(IC7A--IN)") (class "Default")
      (node (ref "IC7") (pin "2") (pinfunction "-IN_2") (pintype "input"))
      (node (ref "R20") (pin "2") (pinfunction "2_2") (pintype "passive"))
      (node (ref "R21") (pin "1") (pinfunction "1_1") (pintype "passive"))
    )
    (net (code "52") (name "Net-(IC7A-OUT)") (class "Default")
      (node (ref "IC7") (pin "1") (pinfunction "OUT_1") (pintype "output"))
      (node (ref "R19") (pin "2") (pinfunction "2_2") (pintype "passive"))
      (node (ref "R21") (pin "2") (pinfunction "2_2") (pintype "passive"))
    )
    (net (code "53") (name "Net-(IC7B-+IN)") (class "Default")
      (node (ref "IC7") (pin "5") (pinfunction "+IN_5") (pintype "input"))
      (node (ref "R47") (pin "2") (pinfunction "2_2") (pintype "passive"))
    )
    (net (code "54") (name "Net-(IC7B--IN)") (class "Default")
      (node (ref "IC7") (pin "6") (pinfunction "-IN_6") (pintype "input"))
      (node (ref "R19") (pin "1") (pinfunction "1_1") (pintype "passive"))
      (node (ref "R29") (pin "1") (pinfunction "1_1") (pintype "passive"))
    )
    (net (code "55") (name "Net-(IC7B-OUT)") (class "Default")
      (node (ref "IC7") (pin "7") (pinfunction "OUT_7") (pintype "output"))
      (node (ref "R39") (pin "1") (pinfunction "1_1") (pintype "passive"))
      (node (ref "R41") (pin "1") (pinfunction "1_1") (pintype "passive"))
      (node (ref "VR4") (pin "2'") (pinfunction "1_2_2'") (pintype "passive"))
      (node (ref "VR4") (pin "3'") (pinfunction "1_3_3'") (pintype "passive"))
    )
    (net (code "56") (name "Net-(J1-Pad1)") (class "Default")
      (node (ref "J1") (pin "1") (pinfunction "1_1") (pintype "passive"))
      (node (ref "R1") (pin "1") (pinfunction "1_1") (pintype "passive"))
    )
    (net (code "57") (name "Net-(J1-Pad2)") (class "Default")
      (node (ref "J1") (pin "2") (pinfunction "2_2") (pintype "passive"))
      (node (ref "R2") (pin "1") (pinfunction "1_1") (pintype "passive"))
    )
    (net (code "58") (name "Net-(J2-Pad1)") (class "Default")
      (node (ref "J2") (pin "1") (pinfunction "1_1") (pintype "passive"))
      (node (ref "R40") (pin "2") (pinfunction "2_2") (pintype "passive"))
      (node (ref "R88") (pin "2") (pinfunction "2_2") (pintype "passive"))
      (node (ref "R89") (pin "2") (pinfunction "2_2") (pintype "passive"))
    )
    (net (code "59") (name "Net-(J2-Pad2)") (class "Default")
      (node (ref "J2") (pin "2") (pinfunction "2_2") (pintype "passive"))
      (node (ref "R41") (pin "2") (pinfunction "2_2") (pintype "passive"))
      (node (ref "R90") (pin "2") (pinfunction "2_2") (pintype "passive"))
    )
    (net (code "60") (name "Net-(J2-Pad3)") (class "Default")
      (node (ref "J2") (pin "3") (pinfunction "3_3") (pintype "passive"))
      (node (ref "R39") (pin "2") (pinfunction "2_2") (pintype "passive"))
      (node (ref "R91") (pin "2") (pinfunction "2_2") (pintype "passive"))
      (node (ref "R92") (pin "2") (pinfunction "2_2") (pintype "passive"))
    )
    (net (code "61") (name "Net-(VR2A-1_1)") (class "Default")
      (node (ref "R18") (pin "2") (pinfunction "2_2") (pintype "passive"))
      (node (ref "VR2") (pin "1") (pinfunction "1_1_1") (pintype "passive"))
    )
    (net (code "62") (name "Net-(VR2B-1_1)") (class "Default")
      (node (ref "R37") (pin "2") (pinfunction "2_2") (pintype "passive"))
      (node (ref "VR2") (pin "1'") (pinfunction "1_1_1'") (pintype "passive"))
    )
    (net (code "63") (name "Net-(VR3A-1_1)") (class "Default")
      (node (ref "R35") (pin "2") (pinfunction "2_2") (pintype "passive"))
      (node (ref "VR3") (pin "1") (pinfunction "1_1_1") (pintype "passive"))
    )
    (net (code "64") (name "Net-(VR3B-1_1)") (class "Default")
      (node (ref "R30") (pin "2") (pinfunction "2_2") (pintype "passive"))
      (node (ref "VR3") (pin "1'") (pinfunction "1_1_1'") (pintype "passive"))
    )
    (net (code "65") (name "Net-(VR4A-1_1)") (class "Default")
      (node (ref "R34") (pin "2") (pinfunction "2_2") (pintype "passive"))
      (node (ref "VR4") (pin "1") (pinfunction "1_1_1") (pintype "passive"))
    )
    (net (code "66") (name "Net-(VR4B-1_1)") (class "Default")
      (node (ref "R29") (pin "2") (pinfunction "2_2") (pintype "passive"))
      (node (ref "VR4") (pin "1'") (pinfunction "1_1_1'") (pintype "passive"))
    )
  )
)
